# stm32f407z.net
KiCad netlist of a schematic drawn in Altium Designer
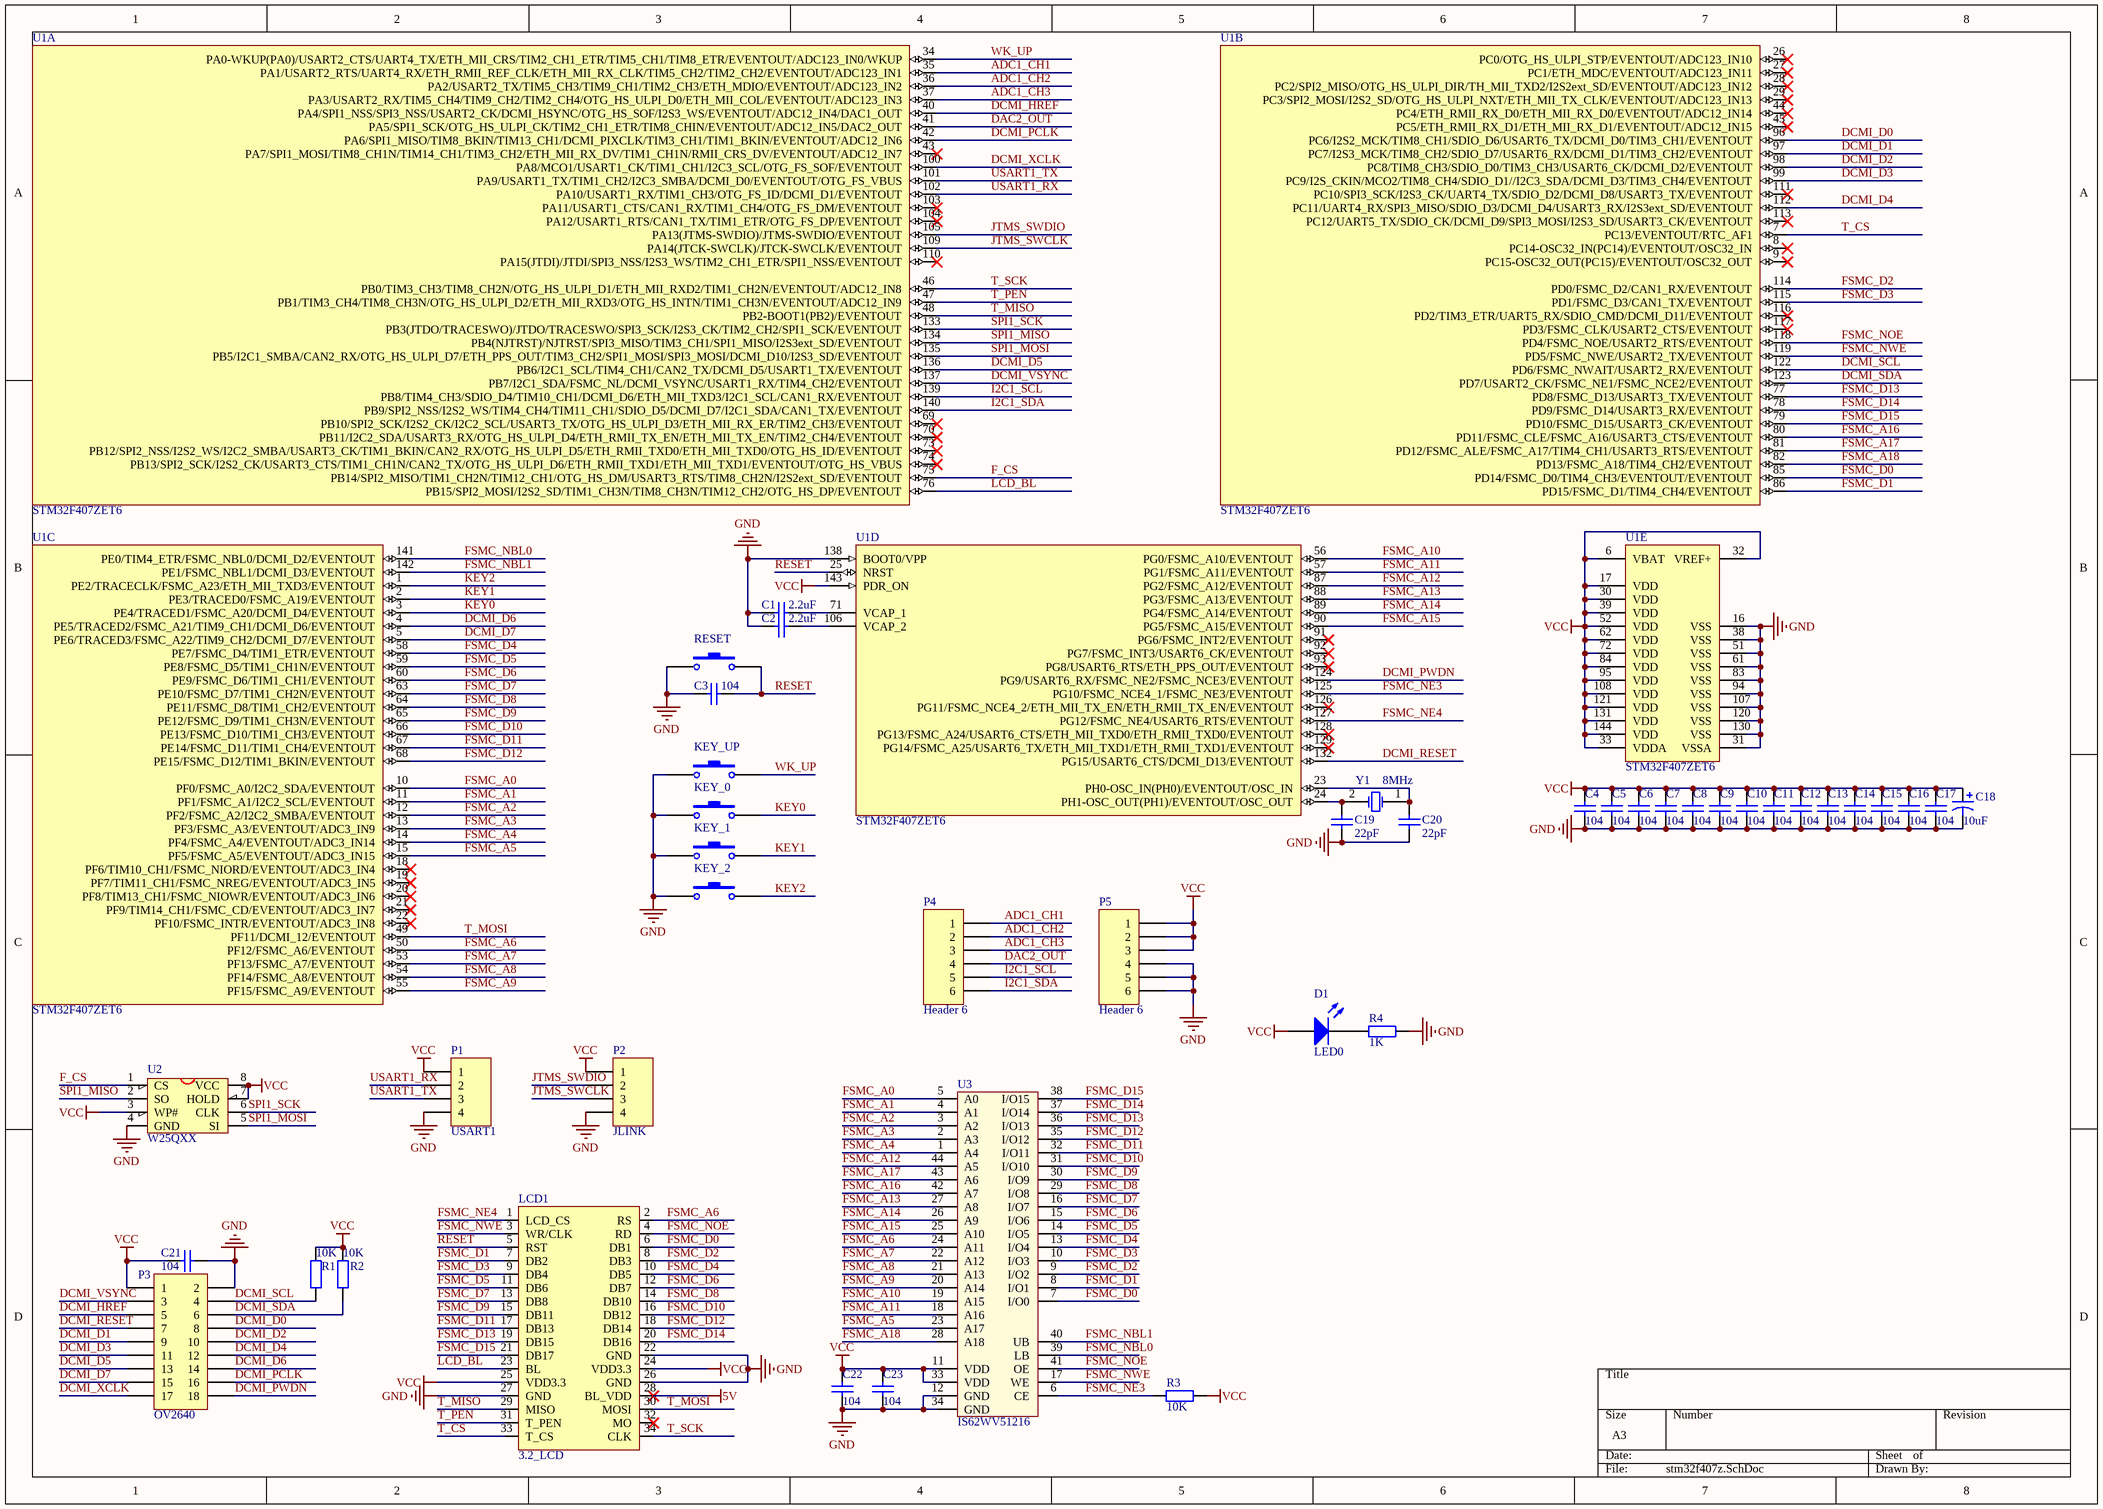
[diagram p0: stm32f407z.SchDoc]

(export (version "E")
  (design (tool "Eeschema 10.0.6"))
  (components
    (comp (ref "C1")
      (value "2.2uF")
      (footprint "C0603")
      (description "Capacitor")
      (libsource (lib "Miscellaneous Devices") (part "Cap"))
    )
    (comp (ref "C2")
      (value "2.2uF")
      (footprint "C0603")
      (description "Capacitor")
      (libsource (lib "Miscellaneous Devices") (part "Cap"))
    )
    (comp (ref "C3")
      (value "104")
      (footprint "C0603")
      (description "Capacitor")
      (libsource (lib "Miscellaneous Devices") (part "Cap"))
    )
    (comp (ref "C4")
      (value "104")
      (footprint "C0603")
      (description "Capacitor")
      (libsource (lib "Miscellaneous Devices") (part "Cap"))
    )
    (comp (ref "C5")
      (value "104")
      (footprint "C0603")
      (description "Capacitor")
      (libsource (lib "Miscellaneous Devices") (part "Cap"))
    )
    (comp (ref "C6")
      (value "104")
      (footprint "C0603")
      (description "Capacitor")
      (libsource (lib "Miscellaneous Devices") (part "Cap"))
    )
    (comp (ref "C7")
      (value "104")
      (footprint "C0603")
      (description "Capacitor")
      (libsource (lib "Miscellaneous Devices") (part "Cap"))
    )
    (comp (ref "C8")
      (value "104")
      (footprint "C0603")
      (description "Capacitor")
      (libsource (lib "Miscellaneous Devices") (part "Cap"))
    )
    (comp (ref "C9")
      (value "104")
      (footprint "C0603")
      (description "Capacitor")
      (libsource (lib "Miscellaneous Devices") (part "Cap"))
    )
    (comp (ref "C10")
      (value "104")
      (footprint "C0603")
      (description "Capacitor")
      (libsource (lib "Miscellaneous Devices") (part "Cap"))
    )
    (comp (ref "C11")
      (value "104")
      (footprint "C0603")
      (description "Capacitor")
      (libsource (lib "Miscellaneous Devices") (part "Cap"))
    )
    (comp (ref "C12")
      (value "104")
      (footprint "C0603")
      (description "Capacitor")
      (libsource (lib "Miscellaneous Devices") (part "Cap"))
    )
    (comp (ref "C13")
      (value "104")
      (footprint "C0603")
      (description "Capacitor")
      (libsource (lib "Miscellaneous Devices") (part "Cap"))
    )
    (comp (ref "C14")
      (value "104")
      (footprint "C0603")
      (description "Capacitor")
      (libsource (lib "Miscellaneous Devices") (part "Cap"))
    )
    (comp (ref "C15")
      (value "104")
      (footprint "C0603")
      (description "Capacitor")
      (libsource (lib "Miscellaneous Devices") (part "Cap"))
    )
    (comp (ref "C16")
      (value "104")
      (footprint "C0603")
      (description "Capacitor")
      (libsource (lib "Miscellaneous Devices") (part "Cap"))
    )
    (comp (ref "C17")
      (value "104")
      (footprint "C0603")
      (description "Capacitor")
      (libsource (lib "Miscellaneous Devices") (part "Cap"))
    )
    (comp (ref "C18")
      (value "10uF")
      (footprint "LC-CASE-A_3216")
      (description "Polarized Capacitor (Radial)")
      (libsource (lib "Miscellaneous Devices") (part "Cap Pol1"))
    )
    (comp (ref "C19")
      (value "22pF")
      (footprint "C0603")
      (description "Capacitor")
      (libsource (lib "Miscellaneous Devices") (part "Cap"))
    )
    (comp (ref "C20")
      (value "22pF")
      (footprint "C0603")
      (description "Capacitor")
      (libsource (lib "Miscellaneous Devices") (part "Cap"))
    )
    (comp (ref "C21")
      (value "104")
      (footprint "C0603")
      (description "Capacitor")
      (libsource (lib "Miscellaneous Devices") (part "Cap"))
    )
    (comp (ref "C22")
      (value "104")
      (footprint "C0603")
      (description "Capacitor")
      (libsource (lib "Miscellaneous Devices") (part "Cap"))
    )
    (comp (ref "C23")
      (value "104")
      (footprint "C0603")
      (description "Capacitor")
      (libsource (lib "Miscellaneous Devices") (part "Cap"))
    )
    (comp (ref "D1")
      (value "LED0")
      (footprint "LED0603")
      (description "Typical INFRARED GaAs LED")
      (libsource (lib "Miscellaneous Devices") (part "LED0"))
    )
    (comp (ref "KEY_0")
      (value "RESET")
      (footprint "micro button_2_SMD")
      (description "Switch")
      (libsource (lib "Miscellaneous Devices") (part "SW-PB"))
    )
    (comp (ref "KEY_1")
      (value "RESET")
      (footprint "micro button_2_SMD")
      (description "Switch")
      (libsource (lib "Miscellaneous Devices") (part "SW-PB"))
    )
    (comp (ref "KEY_2")
      (value "RESET")
      (footprint "micro button_2_SMD")
      (description "Switch")
      (libsource (lib "Miscellaneous Devices") (part "SW-PB"))
    )
    (comp (ref "KEY_UP")
      (value "RESET")
      (footprint "micro button_2_SMD")
      (description "Switch")
      (libsource (lib "Miscellaneous Devices") (part "SW-PB"))
    )
    (comp (ref "LCD1") (value "3.2_LCD") (footprint "HDR2X17") (libsource (lib "主控板载芯片") (part "3.2_LCD")))
    (comp (ref "P1")
      (value "USART1")
      (footprint "1.25PWT-4P")
      (description "Header, 4-Pin")
      (libsource (lib "Miscellaneous Connectors") (part "Header 4"))
    )
    (comp (ref "P2")
      (value "JLINK")
      (footprint "1.25PWT-4P")
      (description "Header, 4-Pin")
      (libsource (lib "Miscellaneous Connectors") (part "Header 4"))
    )
    (comp (ref "P3")
      (value "OV2640")
      (footprint "HDR2X9")
      (description "Header, 9-Pin, Dual row")
      (libsource (lib "Miscellaneous Connectors") (part "Header 9X2"))
    )
    (comp (ref "P4")
      (value "Header 6")
      (footprint "PIN_6")
      (description "Header, 6-Pin")
      (libsource (lib "Miscellaneous Connectors") (part "Header 6"))
    )
    (comp (ref "P5")
      (value "Header 6")
      (footprint "PIN_6")
      (description "Header, 6-Pin")
      (libsource (lib "Miscellaneous Connectors") (part "Header 6"))
    )
    (comp (ref "R1")
      (value "10K")
      (footprint "R0603")
      (description "Resistor")
      (libsource (lib "Miscellaneous Devices") (part "Res2"))
    )
    (comp (ref "R2")
      (value "10K")
      (footprint "R0603")
      (description "Resistor")
      (libsource (lib "Miscellaneous Devices") (part "Res2"))
    )
    (comp (ref "R3")
      (value "10K")
      (footprint "R0603")
      (description "Resistor")
      (libsource (lib "") (part "Res2_1"))
    )
    (comp (ref "R4")
      (value "1K")
      (footprint "R0603")
      (description "Resistor")
      (libsource (lib "") (part "Res2_1"))
    )
    (comp (ref "RESET")
      (value "RESET")
      (footprint "micro button_2_SMD")
      (description "Switch")
      (libsource (lib "Miscellaneous Devices") (part "SW-PB"))
    )
    (comp (ref "U1")
      (value "STM32F407ZET6")
      (footprint "QFP144-0r5-20X20")
      (libsource (lib "STMicroelectronics STM32 F4") (part "STM32F407ZET6"))
    )
    (comp (ref "U2")
      (value "W25QXX")
      (footprint "SOIC_8")
      (description "W25X16;SST25VF016;MX25L1605")
      (libsource (lib "战舰STM32开发板底板封装库") (part "W25X16"))
    )
    (comp (ref "U3")
      (value "IS62WV51216")
      (footprint "TSOP44-0r8-10")
      (libsource (lib "Explorer STM32F407封装库") (part "IS62WV51216"))
    )
    (comp (ref "Y1")
      (value "8MHz")
      (footprint "Crystal_HC_49USMD")
      (description "Crystal Oscillator")
      (libsource (lib "Miscellaneous Devices") (part "XTAL"))
    )
  )
  (nets
    (net (code "1") (name "/ADC1_CH1") (class "Default")
      (node (ref "P4") (pin "1") (pinfunction "1_1") (pintype "passive"))
      (node (ref "U1") (pin "35") (pinfunction "PA1/USART2_RTS/UART4_RX/ETH_RMII_REF_CLK/ETH_MII_RX_CLK/TIM5_CH2/TIM2_CH2/EVENTOUT/ADC123_IN1_35") (pintype "bidirectional"))
    )
    (net (code "2") (name "/ADC1_CH2") (class "Default")
      (node (ref "P4") (pin "2") (pinfunction "2_2") (pintype "passive"))
      (node (ref "U1") (pin "36") (pinfunction "PA2/USART2_TX/TIM5_CH3/TIM9_CH1/TIM2_CH3/ETH_MDIO/EVENTOUT/ADC123_IN2_36") (pintype "bidirectional"))
    )
    (net (code "3") (name "/ADC1_CH3") (class "Default")
      (node (ref "P4") (pin "3") (pinfunction "3_3") (pintype "passive"))
      (node (ref "U1") (pin "37") (pinfunction "PA3/USART2_RX/TIM5_CH4/TIM9_CH2/TIM2_CH4/OTG_HS_ULPI_D0/ETH_MII_COL/EVENTOUT/ADC123_IN3_37") (pintype "bidirectional"))
    )
    (net (code "4") (name "/DAC2_OUT") (class "Default")
      (node (ref "P4") (pin "4") (pinfunction "4_4") (pintype "passive"))
      (node (ref "U1") (pin "41") (pinfunction "PA5/SPI1_SCK/OTG_HS_ULPI_CK/TIM2_CH1_ETR/TIM8_CHIN/EVENTOUT/ADC12_IN5/DAC2_OUT_41") (pintype "bidirectional"))
    )
    (net (code "5") (name "/DCMI_D0") (class "Default")
      (node (ref "P3") (pin "8") (pinfunction "8_8") (pintype "passive"))
      (node (ref "U1") (pin "96") (pinfunction "PC6/I2S2_MCK/TIM8_CH1/SDIO_D6/USART6_TX/DCMI_D0/TIM3_CH1/EVENTOUT_96") (pintype "bidirectional"))
    )
    (net (code "6") (name "/DCMI_D1") (class "Default")
      (node (ref "P3") (pin "9") (pinfunction "9_9") (pintype "passive"))
      (node (ref "U1") (pin "97") (pinfunction "PC7/I2S3_MCK/TIM8_CH2/SDIO_D7/USART6_RX/DCMI_D1/TIM3_CH2/EVENTOUT_97") (pintype "bidirectional"))
    )
    (net (code "7") (name "/DCMI_D2") (class "Default")
      (node (ref "P3") (pin "10") (pinfunction "10_10") (pintype "passive"))
      (node (ref "U1") (pin "98") (pinfunction "PC8/TIM8_CH3/SDIO_D0/TIM3_CH3/USART6_CK/DCMI_D2/EVENTOUT_98") (pintype "bidirectional"))
    )
    (net (code "8") (name "/DCMI_D3") (class "Default")
      (node (ref "P3") (pin "11") (pinfunction "11_11") (pintype "passive"))
      (node (ref "U1") (pin "99") (pinfunction "PC9/I2S_CKIN/MCO2/TIM8_CH4/SDIO_D1//I2C3_SDA/DCMI_D3/TIM3_CH4/EVENTOUT_99") (pintype "bidirectional"))
    )
    (net (code "9") (name "/DCMI_D4") (class "Default")
      (node (ref "P3") (pin "12") (pinfunction "12_12") (pintype "passive"))
      (node (ref "U1") (pin "112") (pinfunction "PC11/UART4_RX/SPI3_MISO/SDIO_D3/DCMI_D4/USART3_RX/I2S3ext_SD/EVENTOUT_112") (pintype "bidirectional"))
    )
    (net (code "10") (name "/DCMI_D5") (class "Default")
      (node (ref "P3") (pin "13") (pinfunction "13_13") (pintype "passive"))
      (node (ref "U1") (pin "136") (pinfunction "PB6/I2C1_SCL/TIM4_CH1/CAN2_TX/DCMI_D5/USART1_TX/EVENTOUT_136") (pintype "bidirectional"))
    )
    (net (code "11") (name "/DCMI_D6") (class "Default")
      (node (ref "P3") (pin "14") (pinfunction "14_14") (pintype "passive"))
      (node (ref "U1") (pin "4") (pinfunction "PE5/TRACED2/FSMC_A21/TIM9_CH1/DCMI_D6/EVENTOUT_4") (pintype "bidirectional"))
    )
    (net (code "12") (name "/DCMI_D7") (class "Default")
      (node (ref "P3") (pin "15") (pinfunction "15_15") (pintype "passive"))
      (node (ref "U1") (pin "5") (pinfunction "PE6/TRACED3/FSMC_A22/TIM9_CH2/DCMI_D7/EVENTOUT_5") (pintype "bidirectional"))
    )
    (net (code "13") (name "/DCMI_HREF") (class "Default")
      (node (ref "P3") (pin "5") (pinfunction "5_5") (pintype "passive"))
      (node (ref "U1") (pin "40") (pinfunction "PA4/SPI1_NSS/SPI3_NSS/USART2_CK/DCMI_HSYNC/OTG_HS_SOF/I2S3_WS/EVENTOUT/ADC12_IN4/DAC1_OUT_40") (pintype "bidirectional"))
    )
    (net (code "14") (name "/DCMI_PCLK") (class "Default")
      (node (ref "P3") (pin "16") (pinfunction "16_16") (pintype "passive"))
      (node (ref "U1") (pin "42") (pinfunction "PA6/SPI1_MISO/TIM8_BKIN/TIM13_CH1/DCMI_PIXCLK/TIM3_CH1/TIM1_BKIN/EVENTOUT/ADC12_IN6_42") (pintype "bidirectional"))
    )
    (net (code "15") (name "/DCMI_PWDN") (class "Default")
      (node (ref "P3") (pin "18") (pinfunction "18_18") (pintype "passive"))
      (node (ref "U1") (pin "124") (pinfunction "PG9/USART6_RX/FSMC_NE2/FSMC_NCE3/EVENTOUT_124") (pintype "bidirectional"))
    )
    (net (code "16") (name "/DCMI_RESET") (class "Default")
      (node (ref "P3") (pin "7") (pinfunction "7_7") (pintype "passive"))
      (node (ref "U1") (pin "132") (pinfunction "PG15/USART6_CTS/DCMI_D13/EVENTOUT_132") (pintype "bidirectional"))
    )
    (net (code "17") (name "/DCMI_SCL") (class "Default")
      (node (ref "P3") (pin "4") (pinfunction "4_4") (pintype "passive"))
      (node (ref "R1") (pin "1") (pinfunction "1_1") (pintype "passive"))
      (node (ref "U1") (pin "122") (pinfunction "PD6/FSMC_NWAIT/USART2_RX/EVENTOUT_122") (pintype "bidirectional"))
    )
    (net (code "18") (name "/DCMI_SDA") (class "Default")
      (node (ref "P3") (pin "6") (pinfunction "6_6") (pintype "passive"))
      (node (ref "R2") (pin "1") (pinfunction "1_1") (pintype "passive"))
      (node (ref "U1") (pin "123") (pinfunction "PD7/USART2_CK/FSMC_NE1/FSMC_NCE2/EVENTOUT_123") (pintype "bidirectional"))
    )
    (net (code "19") (name "/DCMI_VSYNC") (class "Default")
      (node (ref "P3") (pin "3") (pinfunction "3_3") (pintype "passive"))
      (node (ref "U1") (pin "137") (pinfunction "PB7/I2C1_SDA/FSMC_NL/DCMI_VSYNC/USART1_RX/TIM4_CH2/EVENTOUT_137") (pintype "bidirectional"))
    )
    (net (code "20") (name "/DCMI_XCLK") (class "Default")
      (node (ref "P3") (pin "17") (pinfunction "17_17") (pintype "passive"))
      (node (ref "U1") (pin "100") (pinfunction "PA8/MCO1/USART1_CK/TIM1_CH1/I2C3_SCL/OTG_FS_SOF/EVENTOUT_100") (pintype "bidirectional"))
    )
    (net (code "21") (name "/FSMC_A0") (class "Default")
      (node (ref "U1") (pin "10") (pinfunction "PF0/FSMC_A0/I2C2_SDA/EVENTOUT_10") (pintype "bidirectional"))
      (node (ref "U3") (pin "5") (pinfunction "A0_5") (pintype "passive"))
    )
    (net (code "22") (name "/FSMC_A1") (class "Default")
      (node (ref "U1") (pin "11") (pinfunction "PF1/FSMC_A1/I2C2_SCL/EVENTOUT_11") (pintype "bidirectional"))
      (node (ref "U3") (pin "4") (pinfunction "A1_4") (pintype "passive"))
    )
    (net (code "23") (name "/FSMC_A2") (class "Default")
      (node (ref "U1") (pin "12") (pinfunction "PF2/FSMC_A2/I2C2_SMBA/EVENTOUT_12") (pintype "bidirectional"))
      (node (ref "U3") (pin "3") (pinfunction "A2_3") (pintype "passive"))
    )
    (net (code "24") (name "/FSMC_A3") (class "Default")
      (node (ref "U1") (pin "13") (pinfunction "PF3/FSMC_A3/EVENTOUT/ADC3_IN9_13") (pintype "bidirectional"))
      (node (ref "U3") (pin "2") (pinfunction "A3_2") (pintype "passive"))
    )
    (net (code "25") (name "/FSMC_A4") (class "Default")
      (node (ref "U1") (pin "14") (pinfunction "PF4/FSMC_A4/EVENTOUT/ADC3_IN14_14") (pintype "bidirectional"))
      (node (ref "U3") (pin "1") (pinfunction "A4_1") (pintype "passive"))
    )
    (net (code "26") (name "/FSMC_A5") (class "Default")
      (node (ref "U1") (pin "15") (pinfunction "PF5/FSMC_A5/EVENTOUT/ADC3_IN15_15") (pintype "bidirectional"))
      (node (ref "U3") (pin "23") (pinfunction "A17_23") (pintype "passive"))
    )
    (net (code "27") (name "/FSMC_A6") (class "Default")
      (node (ref "LCD1") (pin "2") (pinfunction "RS_2") (pintype "passive"))
      (node (ref "U1") (pin "50") (pinfunction "PF12/FSMC_A6/EVENTOUT_50") (pintype "bidirectional"))
      (node (ref "U3") (pin "24") (pinfunction "A11_24") (pintype "passive"))
    )
    (net (code "28") (name "/FSMC_A7") (class "Default")
      (node (ref "U1") (pin "53") (pinfunction "PF13/FSMC_A7/EVENTOUT_53") (pintype "bidirectional"))
      (node (ref "U3") (pin "22") (pinfunction "A12_22") (pintype "passive"))
    )
    (net (code "29") (name "/FSMC_A8") (class "Default")
      (node (ref "U1") (pin "54") (pinfunction "PF14/FSMC_A8/EVENTOUT_54") (pintype "bidirectional"))
      (node (ref "U3") (pin "21") (pinfunction "A13_21") (pintype "passive"))
    )
    (net (code "30") (name "/FSMC_A9") (class "Default")
      (node (ref "U1") (pin "55") (pinfunction "PF15/FSMC_A9/EVENTOUT_55") (pintype "bidirectional"))
      (node (ref "U3") (pin "20") (pinfunction "A14_20") (pintype "passive"))
    )
    (net (code "31") (name "/FSMC_A10") (class "Default")
      (node (ref "U1") (pin "56") (pinfunction "PG0/FSMC_A10/EVENTOUT_56") (pintype "bidirectional"))
      (node (ref "U3") (pin "19") (pinfunction "A15_19") (pintype "passive"))
    )
    (net (code "32") (name "/FSMC_A11") (class "Default")
      (node (ref "U1") (pin "57") (pinfunction "PG1/FSMC_A11/EVENTOUT_57") (pintype "bidirectional"))
      (node (ref "U3") (pin "18") (pinfunction "A16_18") (pintype "passive"))
    )
    (net (code "33") (name "/FSMC_A12") (class "Default")
      (node (ref "U1") (pin "87") (pinfunction "PG2/FSMC_A12/EVENTOUT_87") (pintype "bidirectional"))
      (node (ref "U3") (pin "44") (pinfunction "A5_44") (pintype "passive"))
    )
    (net (code "34") (name "/FSMC_A13") (class "Default")
      (node (ref "U1") (pin "88") (pinfunction "PG3/FSMC_A13/EVENTOUT_88") (pintype "bidirectional"))
      (node (ref "U3") (pin "27") (pinfunction "A8_27") (pintype "passive"))
    )
    (net (code "35") (name "/FSMC_A14") (class "Default")
      (node (ref "U1") (pin "89") (pinfunction "PG4/FSMC_A14/EVENTOUT_89") (pintype "bidirectional"))
      (node (ref "U3") (pin "26") (pinfunction "A9_26") (pintype "passive"))
    )
    (net (code "36") (name "/FSMC_A15") (class "Default")
      (node (ref "U1") (pin "90") (pinfunction "PG5/FSMC_A15/EVENTOUT_90") (pintype "bidirectional"))
      (node (ref "U3") (pin "25") (pinfunction "A10_25") (pintype "passive"))
    )
    (net (code "37") (name "/FSMC_A16") (class "Default")
      (node (ref "U1") (pin "80") (pinfunction "PD11/FSMC_CLE/FSMC_A16/USART3_CTS/EVENTOUT_80") (pintype "bidirectional"))
      (node (ref "U3") (pin "42") (pinfunction "A7_42") (pintype "passive"))
    )
    (net (code "38") (name "/FSMC_A17") (class "Default")
      (node (ref "U1") (pin "81") (pinfunction "PD12/FSMC_ALE/FSMC_A17/TIM4_CH1/USART3_RTS/EVENTOUT_81") (pintype "bidirectional"))
      (node (ref "U3") (pin "43") (pinfunction "A6_43") (pintype "passive"))
    )
    (net (code "39") (name "/FSMC_A18") (class "Default")
      (node (ref "U1") (pin "82") (pinfunction "PD13/FSMC_A18/TIM4_CH2/EVENTOUT_82") (pintype "bidirectional"))
      (node (ref "U3") (pin "28") (pinfunction "A18_28") (pintype "passive"))
    )
    (net (code "40") (name "/FSMC_D0") (class "Default")
      (node (ref "LCD1") (pin "6") (pinfunction "DB1_6") (pintype "passive"))
      (node (ref "U1") (pin "85") (pinfunction "PD14/FSMC_D0/TIM4_CH3/EVENTOUT/EVENTOUT_85") (pintype "bidirectional"))
      (node (ref "U3") (pin "7") (pinfunction "I/O0_7") (pintype "passive"))
    )
    (net (code "41") (name "/FSMC_D1") (class "Default")
      (node (ref "LCD1") (pin "7") (pinfunction "DB2_7") (pintype "passive"))
      (node (ref "U1") (pin "86") (pinfunction "PD15/FSMC_D1/TIM4_CH4/EVENTOUT_86") (pintype "bidirectional"))
      (node (ref "U3") (pin "8") (pinfunction "I/O1_8") (pintype "passive"))
    )
    (net (code "42") (name "/FSMC_D2") (class "Default")
      (node (ref "LCD1") (pin "8") (pinfunction "DB3_8") (pintype "passive"))
      (node (ref "U1") (pin "114") (pinfunction "PD0/FSMC_D2/CAN1_RX/EVENTOUT_114") (pintype "bidirectional"))
      (node (ref "U3") (pin "9") (pinfunction "I/O2_9") (pintype "passive"))
    )
    (net (code "43") (name "/FSMC_D3") (class "Default")
      (node (ref "LCD1") (pin "9") (pinfunction "DB4_9") (pintype "passive"))
      (node (ref "U1") (pin "115") (pinfunction "PD1/FSMC_D3/CAN1_TX/EVENTOUT_115") (pintype "bidirectional"))
      (node (ref "U3") (pin "10") (pinfunction "I/O3_10") (pintype "passive"))
    )
    (net (code "44") (name "/FSMC_D4") (class "Default")
      (node (ref "LCD1") (pin "10") (pinfunction "DB5_10") (pintype "passive"))
      (node (ref "U1") (pin "58") (pinfunction "PE7/FSMC_D4/TIM1_ETR/EVENTOUT_58") (pintype "bidirectional"))
      (node (ref "U3") (pin "13") (pinfunction "I/O4_13") (pintype "passive"))
    )
    (net (code "45") (name "/FSMC_D5") (class "Default")
      (node (ref "LCD1") (pin "11") (pinfunction "DB6_11") (pintype "passive"))
      (node (ref "U1") (pin "59") (pinfunction "PE8/FSMC_D5/TIM1_CH1N/EVENTOUT_59") (pintype "bidirectional"))
      (node (ref "U3") (pin "14") (pinfunction "I/O5_14") (pintype "passive"))
    )
    (net (code "46") (name "/FSMC_D6") (class "Default")
      (node (ref "LCD1") (pin "12") (pinfunction "DB7_12") (pintype "passive"))
      (node (ref "U1") (pin "60") (pinfunction "PE9/FSMC_D6/TIM1_CH1/EVENTOUT_60") (pintype "bidirectional"))
      (node (ref "U3") (pin "15") (pinfunction "I/O6_15") (pintype "passive"))
    )
    (net (code "47") (name "/FSMC_D7") (class "Default")
      (node (ref "LCD1") (pin "13") (pinfunction "DB8_13") (pintype "passive"))
      (node (ref "U1") (pin "63") (pinfunction "PE10/FSMC_D7/TIM1_CH2N/EVENTOUT_63") (pintype "bidirectional"))
      (node (ref "U3") (pin "16") (pinfunction "I/O7_16") (pintype "passive"))
    )
    (net (code "48") (name "/FSMC_D8") (class "Default")
      (node (ref "LCD1") (pin "14") (pinfunction "DB10_14") (pintype "passive"))
      (node (ref "U1") (pin "64") (pinfunction "PE11/FSMC_D8/TIM1_CH2/EVENTOUT_64") (pintype "bidirectional"))
      (node (ref "U3") (pin "29") (pinfunction "I/O8_29") (pintype "passive"))
    )
    (net (code "49") (name "/FSMC_D9") (class "Default")
      (node (ref "LCD1") (pin "15") (pinfunction "DB11_15") (pintype "passive"))
      (node (ref "U1") (pin "65") (pinfunction "PE12/FSMC_D9/TIM1_CH3N/EVENTOUT_65") (pintype "bidirectional"))
      (node (ref "U3") (pin "30") (pinfunction "I/O9_30") (pintype "passive"))
    )
    (net (code "50") (name "/FSMC_D10") (class "Default")
      (node (ref "LCD1") (pin "16") (pinfunction "DB12_16") (pintype "passive"))
      (node (ref "U1") (pin "66") (pinfunction "PE13/FSMC_D10/TIM1_CH3/EVENTOUT_66") (pintype "bidirectional"))
      (node (ref "U3") (pin "31") (pinfunction "I/O10_31") (pintype "passive"))
    )
    (net (code "51") (name "/FSMC_D11") (class "Default")
      (node (ref "LCD1") (pin "17") (pinfunction "DB13_17") (pintype "passive"))
      (node (ref "U1") (pin "67") (pinfunction "PE14/FSMC_D11/TIM1_CH4/EVENTOUT_67") (pintype "bidirectional"))
      (node (ref "U3") (pin "32") (pinfunction "I/O11_32") (pintype "passive"))
    )
    (net (code "52") (name "/FSMC_D12") (class "Default")
      (node (ref "LCD1") (pin "18") (pinfunction "DB14_18") (pintype "passive"))
      (node (ref "U1") (pin "68") (pinfunction "PE15/FSMC_D12/TIM1_BKIN/EVENTOUT_68") (pintype "bidirectional"))
      (node (ref "U3") (pin "35") (pinfunction "I/O12_35") (pintype "passive"))
    )
    (net (code "53") (name "/FSMC_D13") (class "Default")
      (node (ref "LCD1") (pin "19") (pinfunction "DB15_19") (pintype "passive"))
      (node (ref "U1") (pin "77") (pinfunction "PD8/FSMC_D13/USART3_TX/EVENTOUT_77") (pintype "bidirectional"))
      (node (ref "U3") (pin "36") (pinfunction "I/O13_36") (pintype "passive"))
    )
    (net (code "54") (name "/FSMC_D14") (class "Default")
      (node (ref "LCD1") (pin "20") (pinfunction "DB16_20") (pintype "passive"))
      (node (ref "U1") (pin "78") (pinfunction "PD9/FSMC_D14/USART3_RX/EVENTOUT_78") (pintype "bidirectional"))
      (node (ref "U3") (pin "37") (pinfunction "I/O14_37") (pintype "passive"))
    )
    (net (code "55") (name "/FSMC_D15") (class "Default")
      (node (ref "LCD1") (pin "21") (pinfunction "DB17_21") (pintype "passive"))
      (node (ref "U1") (pin "79") (pinfunction "PD10/FSMC_D15/USART3_CK/EVENTOUT_79") (pintype "bidirectional"))
      (node (ref "U3") (pin "38") (pinfunction "I/O15_38") (pintype "passive"))
    )
    (net (code "56") (name "/FSMC_NBL0") (class "Default")
      (node (ref "U1") (pin "141") (pinfunction "PE0/TIM4_ETR/FSMC_NBL0/DCMI_D2/EVENTOUT_141") (pintype "bidirectional"))
      (node (ref "U3") (pin "39") (pinfunction "LB_39") (pintype "passive"))
    )
    (net (code "57") (name "/FSMC_NBL1") (class "Default")
      (node (ref "U1") (pin "142") (pinfunction "PE1/FSMC_NBL1/DCMI_D3/EVENTOUT_142") (pintype "bidirectional"))
      (node (ref "U3") (pin "40") (pinfunction "UB_40") (pintype "passive"))
    )
    (net (code "58") (name "/FSMC_NE3") (class "Default")
      (node (ref "R3") (pin "2") (pinfunction "2_2") (pintype "passive"))
      (node (ref "U1") (pin "125") (pinfunction "PG10/FSMC_NCE4_1/FSMC_NE3/EVENTOUT_125") (pintype "bidirectional"))
      (node (ref "U3") (pin "6") (pinfunction "CE_6") (pintype "passive"))
    )
    (net (code "59") (name "/FSMC_NE4") (class "Default")
      (node (ref "LCD1") (pin "1") (pinfunction "LCD_CS_1") (pintype "passive"))
      (node (ref "U1") (pin "127") (pinfunction "PG12/FSMC_NE4/USART6_RTS/EVENTOUT_127") (pintype "bidirectional"))
    )
    (net (code "60") (name "/FSMC_NOE") (class "Default")
      (node (ref "LCD1") (pin "4") (pinfunction "RD_4") (pintype "passive"))
      (node (ref "U1") (pin "118") (pinfunction "PD4/FSMC_NOE/USART2_RTS/EVENTOUT_118") (pintype "bidirectional"))
      (node (ref "U3") (pin "41") (pinfunction "OE_41") (pintype "passive"))
    )
    (net (code "61") (name "/FSMC_NWE") (class "Default")
      (node (ref "LCD1") (pin "3") (pinfunction "WR/CLK_3") (pintype "passive"))
      (node (ref "U1") (pin "119") (pinfunction "PD5/FSMC_NWE/USART2_TX/EVENTOUT_119") (pintype "bidirectional"))
      (node (ref "U3") (pin "17") (pinfunction "WE_17") (pintype "passive"))
    )
    (net (code "62") (name "/F_CS") (class "Default")
      (node (ref "U1") (pin "75") (pinfunction "PB14/SPI2_MISO/TIM1_CH2N/TIM12_CH1/OTG_HS_DM/USART3_RTS/TIM8_CH2N/I2S2ext_SD/EVENTOUT_75") (pintype "bidirectional"))
      (node (ref "U2") (pin "1") (pinfunction "CS_1") (pintype "passive"))
    )
    (net (code "63") (name "/I2C1_SCL") (class "Default")
      (node (ref "P4") (pin "5") (pinfunction "5_5") (pintype "passive"))
      (node (ref "U1") (pin "139") (pinfunction "PB8/TIM4_CH3/SDIO_D4/TIM10_CH1/DCMI_D6/ETH_MII_TXD3/I2C1_SCL/CAN1_RX/EVENTOUT_139") (pintype "bidirectional"))
    )
    (net (code "64") (name "/I2C1_SDA") (class "Default")
      (node (ref "P4") (pin "6") (pinfunction "6_6") (pintype "passive"))
      (node (ref "U1") (pin "140") (pinfunction "PB9/SPI2_NSS/I2S2_WS/TIM4_CH4/TIM11_CH1/SDIO_D5/DCMI_D7/I2C1_SDA/CAN1_TX/EVENTOUT_140") (pintype "bidirectional"))
    )
    (net (code "65") (name "/JTMS_SWCLK") (class "Default")
      (node (ref "P2") (pin "3") (pinfunction "3_3") (pintype "passive"))
      (node (ref "U1") (pin "109") (pinfunction "PA14(JTCK-SWCLK)/JTCK-SWCLK/EVENTOUT_109") (pintype "bidirectional"))
    )
    (net (code "66") (name "/JTMS_SWDIO") (class "Default")
      (node (ref "P2") (pin "2") (pinfunction "2_2") (pintype "passive"))
      (node (ref "U1") (pin "105") (pinfunction "PA13(JTMS-SWDIO)/JTMS-SWDIO/EVENTOUT_105") (pintype "bidirectional"))
    )
    (net (code "67") (name "/KEY0") (class "Default")
      (node (ref "KEY_0") (pin "2") (pinfunction "2_2") (pintype "passive"))
      (node (ref "U1") (pin "3") (pinfunction "PE4/TRACED1/FSMC_A20/DCMI_D4/EVENTOUT_3") (pintype "bidirectional"))
    )
    (net (code "68") (name "/KEY1") (class "Default")
      (node (ref "KEY_1") (pin "2") (pinfunction "2_2") (pintype "passive"))
      (node (ref "U1") (pin "2") (pinfunction "PE3/TRACED0/FSMC_A19/EVENTOUT_2") (pintype "bidirectional"))
    )
    (net (code "69") (name "/KEY2") (class "Default")
      (node (ref "KEY_2") (pin "2") (pinfunction "2_2") (pintype "passive"))
      (node (ref "U1") (pin "1") (pinfunction "PE2/TRACECLK/FSMC_A23/ETH_MII_TXD3/EVENTOUT_1") (pintype "bidirectional"))
    )
    (net (code "70") (name "/LCD_BL") (class "Default")
      (node (ref "LCD1") (pin "23") (pinfunction "BL_23") (pintype "passive"))
      (node (ref "U1") (pin "76") (pinfunction "PB15/SPI2_MOSI/I2S2_SD/TIM1_CH3N/TIM8_CH3N/TIM12_CH2/OTG_HS_DP/EVENTOUT_76") (pintype "bidirectional"))
    )
    (net (code "71") (name "/RESET") (class "Default")
      (node (ref "C3") (pin "2") (pinfunction "2_2") (pintype "passive"))
      (node (ref "LCD1") (pin "5") (pinfunction "RST_5") (pintype "passive"))
      (node (ref "RESET") (pin "2") (pinfunction "2_2") (pintype "passive"))
      (node (ref "U1") (pin "25") (pinfunction "NRST_25") (pintype "bidirectional"))
    )
    (net (code "72") (name "/SPI1_MISO") (class "Default")
      (node (ref "U1") (pin "134") (pinfunction "PB4(NJTRST)/NJTRST/SPI3_MISO/TIM3_CH1/SPI1_MISO/I2S3ext_SD/EVENTOUT_134") (pintype "bidirectional"))
      (node (ref "U2") (pin "2") (pinfunction "SO_2") (pintype "passive"))
    )
    (net (code "73") (name "/SPI1_MOSI") (class "Default")
      (node (ref "U1") (pin "135") (pinfunction "PB5/I2C1_SMBA/CAN2_RX/OTG_HS_ULPI_D7/ETH_PPS_OUT/TIM3_CH2/SPI1_MOSI/SPI3_MOSI/DCMI_D10/I2S3_SD/EVENTOUT_135") (pintype "bidirectional"))
      (node (ref "U2") (pin "5") (pinfunction "SI_5") (pintype "passive"))
    )
    (net (code "74") (name "/SPI1_SCK") (class "Default")
      (node (ref "U1") (pin "133") (pinfunction "PB3(JTDO/TRACESWO)/JTDO/TRACESWO/SPI3_SCK/I2S3_CK/TIM2_CH2/SPI1_SCK/EVENTOUT_133") (pintype "bidirectional"))
      (node (ref "U2") (pin "6") (pinfunction "CLK_6") (pintype "passive"))
    )
    (net (code "75") (name "/T_CS") (class "Default")
      (node (ref "LCD1") (pin "33") (pinfunction "T_CS_33") (pintype "passive"))
      (node (ref "U1") (pin "7") (pinfunction "PC13/EVENTOUT/RTC_AF1_7") (pintype "bidirectional"))
    )
    (net (code "76") (name "/T_MISO") (class "Default")
      (node (ref "LCD1") (pin "29") (pinfunction "MISO_29") (pintype "passive"))
      (node (ref "U1") (pin "48") (pinfunction "PB2-BOOT1(PB2)/EVENTOUT_48") (pintype "bidirectional"))
    )
    (net (code "77") (name "/T_MOSI") (class "Default")
      (node (ref "LCD1") (pin "30") (pinfunction "MOSI_30") (pintype "passive"))
      (node (ref "U1") (pin "49") (pinfunction "PF11/DCMI_12/EVENTOUT_49") (pintype "bidirectional"))
    )
    (net (code "78") (name "/T_PEN") (class "Default")
      (node (ref "LCD1") (pin "31") (pinfunction "T_PEN_31") (pintype "passive"))
      (node (ref "U1") (pin "47") (pinfunction "PB1/TIM3_CH4/TIM8_CH3N/OTG_HS_ULPI_D2/ETH_MII_RXD3/OTG_HS_INTN/TIM1_CH3N/EVENTOUT/ADC12_IN9_47") (pintype "bidirectional"))
    )
    (net (code "79") (name "/T_SCK") (class "Default")
      (node (ref "LCD1") (pin "34") (pinfunction "CLK_34") (pintype "passive"))
      (node (ref "U1") (pin "46") (pinfunction "PB0/TIM3_CH3/TIM8_CH2N/OTG_HS_ULPI_D1/ETH_MII_RXD2/TIM1_CH2N/EVENTOUT/ADC12_IN8_46") (pintype "bidirectional"))
    )
    (net (code "80") (name "/USART1_RX") (class "Default")
      (node (ref "P1") (pin "2") (pinfunction "2_2") (pintype "passive"))
      (node (ref "U1") (pin "102") (pinfunction "PA10/USART1_RX/TIM1_CH3/OTG_FS_ID/DCMI_D1/EVENTOUT_102") (pintype "bidirectional"))
    )
    (net (code "81") (name "/USART1_TX") (class "Default")
      (node (ref "P1") (pin "3") (pinfunction "3_3") (pintype "passive"))
      (node (ref "U1") (pin "101") (pinfunction "PA9/USART1_TX/TIM1_CH2/I2C3_SMBA/DCMI_D0/EVENTOUT/OTG_FS_VBUS_101") (pintype "bidirectional"))
    )
    (net (code "82") (name "/WK_UP") (class "Default")
      (node (ref "KEY_UP") (pin "2") (pinfunction "2_2") (pintype "passive"))
      (node (ref "U1") (pin "34") (pinfunction "PA0-WKUP(PA0)/USART2_CTS/UART4_TX/ETH_MII_CRS/TIM2_CH1_ETR/TIM5_CH1/TIM8_ETR/EVENTOUT/ADC123_IN0/WKUP_34") (pintype "bidirectional"))
    )
    (net (code "83") (name "5V") (class "Default")
      (node (ref "LCD1") (pin "28") (pinfunction "BL_VDD_28") (pintype "passive"))
    )
    (net (code "84") (name "GND") (class "Default")
      (node (ref "C1") (pin "1") (pinfunction "1_1") (pintype "passive"))
      (node (ref "C10") (pin "1") (pinfunction "1_1") (pintype "passive"))
      (node (ref "C11") (pin "1") (pinfunction "1_1") (pintype "passive"))
      (node (ref "C12") (pin "1") (pinfunction "1_1") (pintype "passive"))
      (node (ref "C13") (pin "1") (pinfunction "1_1") (pintype "passive"))
      (node (ref "C14") (pin "1") (pinfunction "1_1") (pintype "passive"))
      (node (ref "C15") (pin "1") (pinfunction "1_1") (pintype "passive"))
      (node (ref "C16") (pin "1") (pinfunction "1_1") (pintype "passive"))
      (node (ref "C17") (pin "1") (pinfunction "1_1") (pintype "passive"))
      (node (ref "C18") (pin "2") (pinfunction "2_2") (pintype "passive"))
      (node (ref "C19") (pin "1") (pinfunction "1_1") (pintype "passive"))
      (node (ref "C2") (pin "1") (pinfunction "1_1") (pintype "passive"))
      (node (ref "C20") (pin "1") (pinfunction "1_1") (pintype "passive"))
      (node (ref "C21") (pin "1") (pinfunction "1_1") (pintype "passive"))
      (node (ref "C22") (pin "1") (pinfunction "1_1") (pintype "passive"))
      (node (ref "C23") (pin "1") (pinfunction "1_1") (pintype "passive"))
      (node (ref "C3") (pin "1") (pinfunction "1_1") (pintype "passive"))
      (node (ref "C4") (pin "1") (pinfunction "1_1") (pintype "passive"))
      (node (ref "C5") (pin "1") (pinfunction "1_1") (pintype "passive"))
      (node (ref "C6") (pin "1") (pinfunction "1_1") (pintype "passive"))
      (node (ref "C7") (pin "1") (pinfunction "1_1") (pintype "passive"))
      (node (ref "C8") (pin "1") (pinfunction "1_1") (pintype "passive"))
      (node (ref "C9") (pin "1") (pinfunction "1_1") (pintype "passive"))
      (node (ref "KEY_0") (pin "1") (pinfunction "1_1") (pintype "passive"))
      (node (ref "KEY_1") (pin "1") (pinfunction "1_1") (pintype "passive"))
      (node (ref "KEY_2") (pin "1") (pinfunction "1_1") (pintype "passive"))
      (node (ref "KEY_UP") (pin "1") (pinfunction "1_1") (pintype "passive"))
      (node (ref "LCD1") (pin "22") (pinfunction "GND_22") (pintype "passive"))
      (node (ref "LCD1") (pin "26") (pinfunction "GND_26") (pintype "passive"))
      (node (ref "LCD1") (pin "27") (pinfunction "GND_27") (pintype "passive"))
      (node (ref "P1") (pin "4") (pinfunction "4_4") (pintype "passive"))
      (node (ref "P2") (pin "4") (pinfunction "4_4") (pintype "passive"))
      (node (ref "P3") (pin "2") (pinfunction "2_2") (pintype "passive"))
      (node (ref "P5") (pin "4") (pinfunction "4_4") (pintype "passive"))
      (node (ref "P5") (pin "5") (pinfunction "5_5") (pintype "passive"))
      (node (ref "P5") (pin "6") (pinfunction "6_6") (pintype "passive"))
      (node (ref "R4") (pin "1") (pinfunction "1_1") (pintype "passive"))
      (node (ref "RESET") (pin "1") (pinfunction "1_1") (pintype "passive"))
      (node (ref "U1") (pin "107") (pinfunction "VSS_107") (pintype "power_in"))
      (node (ref "U1") (pin "120") (pinfunction "VSS_120") (pintype "power_in"))
      (node (ref "U1") (pin "130") (pinfunction "VSS_130") (pintype "power_in"))
      (node (ref "U1") (pin "138") (pinfunction "BOOT0/VPP_138") (pintype "input"))
      (node (ref "U1") (pin "16") (pinfunction "VSS_16") (pintype "power_in"))
      (node (ref "U1") (pin "31") (pinfunction "VSSA_31") (pintype "power_in"))
      (node (ref "U1") (pin "38") (pinfunction "VSS_38") (pintype "power_in"))
      (node (ref "U1") (pin "51") (pinfunction "VSS_51") (pintype "power_in"))
      (node (ref "U1") (pin "61") (pinfunction "VSS_61") (pintype "power_in"))
      (node (ref "U1") (pin "83") (pinfunction "VSS_83") (pintype "power_in"))
      (node (ref "U1") (pin "94") (pinfunction "VSS_94") (pintype "power_in"))
      (node (ref "U2") (pin "4") (pinfunction "GND_4") (pintype "passive"))
      (node (ref "U3") (pin "12") (pinfunction "GND_12") (pintype "passive"))
      (node (ref "U3") (pin "34") (pinfunction "GND_34") (pintype "passive"))
    )
    (net (code "85") (name "Net-(D1-K)") (class "Default")
      (node (ref "D1") (pin "2") (pinfunction "K_2") (pintype "passive"))
      (node (ref "R4") (pin "2") (pinfunction "2_2") (pintype "passive"))
    )
    (net (code "86") (name "Net-(U1D-PH0-OSC_IN(PH0){slash}EVENTOUT{slash}OSC_IN)") (class "Default")
      (node (ref "C20") (pin "2") (pinfunction "2_2") (pintype "passive"))
      (node (ref "U1") (pin "23") (pinfunction "PH0-OSC_IN(PH0)/EVENTOUT/OSC_IN_23") (pintype "bidirectional"))
      (node (ref "Y1") (pin "1") (pinfunction "OSC1_1") (pintype "passive"))
    )
    (net (code "87") (name "Net-(U1D-PH1-OSC_OUT(PH1){slash}EVENTOUT{slash}OSC_OUT)") (class "Default")
      (node (ref "C19") (pin "2") (pinfunction "2_2") (pintype "passive"))
      (node (ref "U1") (pin "24") (pinfunction "PH1-OSC_OUT(PH1)/EVENTOUT/OSC_OUT_24") (pintype "bidirectional"))
      (node (ref "Y1") (pin "2") (pinfunction "OSC2_2") (pintype "passive"))
    )
    (net (code "88") (name "Net-(U1D-VCAP_1)") (class "Default")
      (node (ref "C1") (pin "2") (pinfunction "2_2") (pintype "passive"))
      (node (ref "U1") (pin "71") (pinfunction "VCAP_1_71") (pintype "power_in"))
    )
    (net (code "89") (name "Net-(U1D-VCAP_2)") (class "Default")
      (node (ref "C2") (pin "2") (pinfunction "2_2") (pintype "passive"))
      (node (ref "U1") (pin "106") (pinfunction "VCAP_2_106") (pintype "power_in"))
    )
    (net (code "90") (name "VCC") (class "Default")
      (node (ref "C10") (pin "2") (pinfunction "2_2") (pintype "passive"))
      (node (ref "C11") (pin "2") (pinfunction "2_2") (pintype "passive"))
      (node (ref "C12") (pin "2") (pinfunction "2_2") (pintype "passive"))
      (node (ref "C13") (pin "2") (pinfunction "2_2") (pintype "passive"))
      (node (ref "C14") (pin "2") (pinfunction "2_2") (pintype "passive"))
      (node (ref "C15") (pin "2") (pinfunction "2_2") (pintype "passive"))
      (node (ref "C16") (pin "2") (pinfunction "2_2") (pintype "passive"))
      (node (ref "C17") (pin "2") (pinfunction "2_2") (pintype "passive"))
      (node (ref "C18") (pin "1") (pinfunction "1_1") (pintype "passive"))
      (node (ref "C21") (pin "2") (pinfunction "2_2") (pintype "passive"))
      (node (ref "C22") (pin "2") (pinfunction "2_2") (pintype "passive"))
      (node (ref "C23") (pin "2") (pinfunction "2_2") (pintype "passive"))
      (node (ref "C4") (pin "2") (pinfunction "2_2") (pintype "passive"))
      (node (ref "C5") (pin "2") (pinfunction "2_2") (pintype "passive"))
      (node (ref "C6") (pin "2") (pinfunction "2_2") (pintype "passive"))
      (node (ref "C7") (pin "2") (pinfunction "2_2") (pintype "passive"))
      (node (ref "C8") (pin "2") (pinfunction "2_2") (pintype "passive"))
      (node (ref "C9") (pin "2") (pinfunction "2_2") (pintype "passive"))
      (node (ref "D1") (pin "1") (pinfunction "A_1") (pintype "passive"))
      (node (ref "LCD1") (pin "24") (pinfunction "VDD3.3_24") (pintype "passive"))
      (node (ref "LCD1") (pin "25") (pinfunction "VDD3.3_25") (pintype "passive"))
      (node (ref "P1") (pin "1") (pinfunction "1_1") (pintype "passive"))
      (node (ref "P2") (pin "1") (pinfunction "1_1") (pintype "passive"))
      (node (ref "P3") (pin "1") (pinfunction "1_1") (pintype "passive"))
      (node (ref "P5") (pin "1") (pinfunction "1_1") (pintype "passive"))
      (node (ref "P5") (pin "2") (pinfunction "2_2") (pintype "passive"))
      (node (ref "P5") (pin "3") (pinfunction "3_3") (pintype "passive"))
      (node (ref "R1") (pin "2") (pinfunction "2_2") (pintype "passive"))
      (node (ref "R2") (pin "2") (pinfunction "2_2") (pintype "passive"))
      (node (ref "R3") (pin "1") (pinfunction "1_1") (pintype "passive"))
      (node (ref "U1") (pin "108") (pinfunction "VDD_108") (pintype "power_in"))
      (node (ref "U1") (pin "121") (pinfunction "VDD_121") (pintype "power_in"))
      (node (ref "U1") (pin "131") (pinfunction "VDD_131") (pintype "power_in"))
      (node (ref "U1") (pin "143") (pinfunction "PDR_ON_143") (pintype "input"))
      (node (ref "U1") (pin "144") (pinfunction "VDD_144") (pintype "power_in"))
      (node (ref "U1") (pin "17") (pinfunction "VDD_17") (pintype "power_in"))
      (node (ref "U1") (pin "30") (pinfunction "VDD_30") (pintype "power_in"))
      (node (ref "U1") (pin "32") (pinfunction "VREF+_32") (pintype "power_in"))
      (node (ref "U1") (pin "33") (pinfunction "VDDA_33") (pintype "power_in"))
      (node (ref "U1") (pin "39") (pinfunction "VDD_39") (pintype "power_in"))
      (node (ref "U1") (pin "52") (pinfunction "VDD_52") (pintype "power_in"))
      (node (ref "U1") (pin "6") (pinfunction "VBAT_6") (pintype "power_in"))
      (node (ref "U1") (pin "62") (pinfunction "VDD_62") (pintype "power_in"))
      (node (ref "U1") (pin "72") (pinfunction "VDD_72") (pintype "power_in"))
      (node (ref "U1") (pin "84") (pinfunction "VDD_84") (pintype "power_in"))
      (node (ref "U1") (pin "95") (pinfunction "VDD_95") (pintype "power_in"))
      (node (ref "U2") (pin "3") (pinfunction "WP#_3") (pintype "passive"))
      (node (ref "U2") (pin "7") (pinfunction "HOLD_7") (pintype "passive"))
      (node (ref "U2") (pin "8") (pinfunction "VCC_8") (pintype "passive"))
      (node (ref "U3") (pin "11") (pinfunction "VDD_11") (pintype "passive"))
      (node (ref "U3") (pin "33") (pinfunction "VDD_33") (pintype "passive"))
    )
    (net (code "91") (name "unconnected-(LCD1-MO-Pad32)") (class "Default")
      (node (ref "LCD1") (pin "32") (pinfunction "MO_32") (pintype "passive+no_connect"))
    )
    (net (code "92") (name "unconnected-(U1A-PA7{slash}SPI1_MOSI{slash}TIM8_CH1N{slash}TIM14_CH1{slash}TIM3_CH2{slash}ETH_MII_RX_DV{slash}TIM1_CH1N{slash}RMII_CRS_DV{slash}EVENTOUT{slash}ADC12_IN7-Pad43)") (class "Default")
      (node (ref "U1") (pin "43") (pinfunction "PA7/SPI1_MOSI/TIM8_CH1N/TIM14_CH1/TIM3_CH2/ETH_MII_RX_DV/TIM1_CH1N/RMII_CRS_DV/EVENTOUT/ADC12_IN7_43") (pintype "bidirectional+no_connect"))
    )
    (net (code "93") (name "unconnected-(U1A-PA11{slash}USART1_CTS{slash}CAN1_RX{slash}TIM1_CH4{slash}OTG_FS_DM{slash}EVENTOUT-Pad103)") (class "Default")
      (node (ref "U1") (pin "103") (pinfunction "PA11/USART1_CTS/CAN1_RX/TIM1_CH4/OTG_FS_DM/EVENTOUT_103") (pintype "bidirectional+no_connect"))
    )
    (net (code "94") (name "unconnected-(U1A-PA12{slash}USART1_RTS{slash}CAN1_TX{slash}TIM1_ETR{slash}OTG_FS_DP{slash}EVENTOUT-Pad104)") (class "Default")
      (node (ref "U1") (pin "104") (pinfunction "PA12/USART1_RTS/CAN1_TX/TIM1_ETR/OTG_FS_DP/EVENTOUT_104") (pintype "bidirectional+no_connect"))
    )
    (net (code "95") (name "unconnected-(U1A-PA15(JTDI){slash}JTDI{slash}SPI3_NSS{slash}I2S3_WS{slash}TIM2_CH1_ETR{slash}SPI1_NSS{slash}EVENTOUT-Pad110)") (class "Default")
      (node (ref "U1") (pin "110") (pinfunction "PA15(JTDI)/JTDI/SPI3_NSS/I2S3_WS/TIM2_CH1_ETR/SPI1_NSS/EVENTOUT_110") (pintype "bidirectional+no_connect"))
    )
    (net (code "96") (name "unconnected-(U1A-PB10{slash}SPI2_SCK{slash}I2S2_CK{slash}I2C2_SCL{slash}USART3_TX{slash}OTG_HS_ULPI_D3{slash}ETH_MII_RX_ER{slash}TIM2_CH3{slash}EVENTOUT-Pad69)") (class "Default")
      (node (ref "U1") (pin "69") (pinfunction "PB10/SPI2_SCK/I2S2_CK/I2C2_SCL/USART3_TX/OTG_HS_ULPI_D3/ETH_MII_RX_ER/TIM2_CH3/EVENTOUT_69") (pintype "bidirectional+no_connect"))
    )
    (net (code "97") (name "unconnected-(U1A-PB11{slash}I2C2_SDA{slash}USART3_RX{slash}OTG_HS_ULPI_D4{slash}ETH_RMII_TX_EN{slash}ETH_MII_TX_EN{slash}TIM2_CH4{slash}EVENTOUT-Pad70)") (class "Default")
      (node (ref "U1") (pin "70") (pinfunction "PB11/I2C2_SDA/USART3_RX/OTG_HS_ULPI_D4/ETH_RMII_TX_EN/ETH_MII_TX_EN/TIM2_CH4/EVENTOUT_70") (pintype "bidirectional+no_connect"))
    )
    (net (code "98") (name "unconnected-(U1A-PB12{slash}SPI2_NSS{slash}I2S2_WS{slash}I2C2_SMBA{slash}USART3_CK{slash}TIM1_BKIN{slash}CAN2_RX{slash}OTG_HS_ULPI_D5{slash}ETH_RMII_TXD0{slash}ETH_MII_TXD0{slash}OTG_HS_ID{slash}EVENTOUT-Pad73)") (class "Default")
      (node (ref "U1") (pin "73") (pinfunction "PB12/SPI2_NSS/I2S2_WS/I2C2_SMBA/USART3_CK/TIM1_BKIN/CAN2_RX/OTG_HS_ULPI_D5/ETH_RMII_TXD0/ETH_MII_TXD0/OTG_HS_ID/EVENTOUT_73") (pintype "bidirectional+no_connect"))
    )
    (net (code "99") (name "unconnected-(U1A-PB13{slash}SPI2_SCK{slash}I2S2_CK{slash}USART3_CTS{slash}TIM1_CH1N{slash}CAN2_TX{slash}OTG_HS_ULPI_D6{slash}ETH_RMII_TXD1{slash}ETH_MII_TXD1{slash}EVENTOUT{slash}OTG_HS_VBUS-Pad74)") (class "Default")
      (node (ref "U1") (pin "74") (pinfunction "PB13/SPI2_SCK/I2S2_CK/USART3_CTS/TIM1_CH1N/CAN2_TX/OTG_HS_ULPI_D6/ETH_RMII_TXD1/ETH_MII_TXD1/EVENTOUT/OTG_HS_VBUS_74") (pintype "bidirectional+no_connect"))
    )
    (net (code "100") (name "unconnected-(U1B-PC0{slash}OTG_HS_ULPI_STP{slash}EVENTOUT{slash}ADC123_IN10-Pad26)") (class "Default")
      (node (ref "U1") (pin "26") (pinfunction "PC0/OTG_HS_ULPI_STP/EVENTOUT/ADC123_IN10_26") (pintype "bidirectional+no_connect"))
    )
    (net (code "101") (name "unconnected-(U1B-PC1{slash}ETH_MDC{slash}EVENTOUT{slash}ADC123_IN11-Pad27)") (class "Default")
      (node (ref "U1") (pin "27") (pinfunction "PC1/ETH_MDC/EVENTOUT/ADC123_IN11_27") (pintype "bidirectional+no_connect"))
    )
    (net (code "102") (name "unconnected-(U1B-PC2{slash}SPI2_MISO{slash}OTG_HS_ULPI_DIR{slash}TH_MII_TXD2{slash}I2S2ext_SD{slash}EVENTOUT{slash}ADC123_IN12-Pad28)") (class "Default")
      (node (ref "U1") (pin "28") (pinfunction "PC2/SPI2_MISO/OTG_HS_ULPI_DIR/TH_MII_TXD2/I2S2ext_SD/EVENTOUT/ADC123_IN12_28") (pintype "bidirectional+no_connect"))
    )
    (net (code "103") (name "unconnected-(U1B-PC3{slash}SPI2_MOSI{slash}I2S2_SD{slash}OTG_HS_ULPI_NXT{slash}ETH_MII_TX_CLK{slash}EVENTOUT{slash}ADC123_IN13-Pad29)") (class "Default")
      (node (ref "U1") (pin "29") (pinfunction "PC3/SPI2_MOSI/I2S2_SD/OTG_HS_ULPI_NXT/ETH_MII_TX_CLK/EVENTOUT/ADC123_IN13_29") (pintype "bidirectional+no_connect"))
    )
    (net (code "104") (name "unconnected-(U1B-PC4{slash}ETH_RMII_RX_D0{slash}ETH_MII_RX_D0{slash}EVENTOUT{slash}ADC12_IN14-Pad44)") (class "Default")
      (node (ref "U1") (pin "44") (pinfunction "PC4/ETH_RMII_RX_D0/ETH_MII_RX_D0/EVENTOUT/ADC12_IN14_44") (pintype "bidirectional+no_connect"))
    )
    (net (code "105") (name "unconnected-(U1B-PC5{slash}ETH_RMII_RX_D1{slash}ETH_MII_RX_D1{slash}EVENTOUT{slash}ADC12_IN15-Pad45)") (class "Default")
      (node (ref "U1") (pin "45") (pinfunction "PC5/ETH_RMII_RX_D1/ETH_MII_RX_D1/EVENTOUT/ADC12_IN15_45") (pintype "bidirectional+no_connect"))
    )
    (net (code "106") (name "unconnected-(U1B-PC10{slash}SPI3_SCK{slash}I2S3_CK{slash}UART4_TX{slash}SDIO_D2{slash}DCMI_D8{slash}USART3_TX{slash}EVENTOUT-Pad111)") (class "Default")
      (node (ref "U1") (pin "111") (pinfunction "PC10/SPI3_SCK/I2S3_CK/UART4_TX/SDIO_D2/DCMI_D8/USART3_TX/EVENTOUT_111") (pintype "bidirectional+no_connect"))
    )
    (net (code "107") (name "unconnected-(U1B-PC12{slash}UART5_TX{slash}SDIO_CK{slash}DCMI_D9{slash}SPI3_MOSI{slash}I2S3_SD{slash}USART3_CK{slash}EVENTOUT-Pad113)") (class "Default")
      (node (ref "U1") (pin "113") (pinfunction "PC12/UART5_TX/SDIO_CK/DCMI_D9/SPI3_MOSI/I2S3_SD/USART3_CK/EVENTOUT_113") (pintype "bidirectional+no_connect"))
    )
    (net (code "108") (name "unconnected-(U1B-PC14-OSC32_IN(PC14){slash}EVENTOUT{slash}OSC32_IN-Pad8)") (class "Default")
      (node (ref "U1") (pin "8") (pinfunction "PC14-OSC32_IN(PC14)/EVENTOUT/OSC32_IN_8") (pintype "bidirectional+no_connect"))
    )
    (net (code "109") (name "unconnected-(U1B-PC15-OSC32_OUT(PC15){slash}EVENTOUT{slash}OSC32_OUT-Pad9)") (class "Default")
      (node (ref "U1") (pin "9") (pinfunction "PC15-OSC32_OUT(PC15)/EVENTOUT/OSC32_OUT_9") (pintype "bidirectional+no_connect"))
    )
    (net (code "110") (name "unconnected-(U1B-PD2{slash}TIM3_ETR{slash}UART5_RX{slash}SDIO_CMD{slash}DCMI_D11{slash}EVENTOUT-Pad116)") (class "Default")
      (node (ref "U1") (pin "116") (pinfunction "PD2/TIM3_ETR/UART5_RX/SDIO_CMD/DCMI_D11/EVENTOUT_116") (pintype "bidirectional+no_connect"))
    )
    (net (code "111") (name "unconnected-(U1B-PD3{slash}FSMC_CLK{slash}USART2_CTS{slash}EVENTOUT-Pad117)") (class "Default")
      (node (ref "U1") (pin "117") (pinfunction "PD3/FSMC_CLK/USART2_CTS/EVENTOUT_117") (pintype "bidirectional+no_connect"))
    )
    (net (code "112") (name "unconnected-(U1C-PF6{slash}TIM10_CH1{slash}FSMC_NIORD{slash}EVENTOUT{slash}ADC3_IN4-Pad18)") (class "Default")
      (node (ref "U1") (pin "18") (pinfunction "PF6/TIM10_CH1/FSMC_NIORD/EVENTOUT/ADC3_IN4_18") (pintype "bidirectional+no_connect"))
    )
    (net (code "113") (name "unconnected-(U1C-PF7{slash}TIM11_CH1{slash}FSMC_NREG{slash}EVENTOUT{slash}ADC3_IN5-Pad19)") (class "Default")
      (node (ref "U1") (pin "19") (pinfunction "PF7/TIM11_CH1/FSMC_NREG/EVENTOUT/ADC3_IN5_19") (pintype "bidirectional+no_connect"))
    )
    (net (code "114") (name "unconnected-(U1C-PF8{slash}TIM13_CH1{slash}FSMC_NIOWR{slash}EVENTOUT{slash}ADC3_IN6-Pad20)") (class "Default")
      (node (ref "U1") (pin "20") (pinfunction "PF8/TIM13_CH1/FSMC_NIOWR/EVENTOUT/ADC3_IN6_20") (pintype "bidirectional+no_connect"))
    )
    (net (code "115") (name "unconnected-(U1C-PF9{slash}TIM14_CH1{slash}FSMC_CD{slash}EVENTOUT{slash}ADC3_IN7-Pad21)") (class "Default")
      (node (ref "U1") (pin "21") (pinfunction "PF9/TIM14_CH1/FSMC_CD/EVENTOUT/ADC3_IN7_21") (pintype "bidirectional+no_connect"))
    )
    (net (code "116") (name "unconnected-(U1C-PF10{slash}FSMC_INTR{slash}EVENTOUT{slash}ADC3_IN8-Pad22)") (class "Default")
      (node (ref "U1") (pin "22") (pinfunction "PF10/FSMC_INTR/EVENTOUT/ADC3_IN8_22") (pintype "bidirectional+no_connect"))
    )
    (net (code "117") (name "unconnected-(U1D-PG6{slash}FSMC_INT2{slash}EVENTOUT-Pad91)") (class "Default")
      (node (ref "U1") (pin "91") (pinfunction "PG6/FSMC_INT2/EVENTOUT_91") (pintype "bidirectional+no_connect"))
    )
    (net (code "118") (name "unconnected-(U1D-PG7{slash}FSMC_INT3{slash}USART6_CK{slash}EVENTOUT-Pad92)") (class "Default")
      (node (ref "U1") (pin "92") (pinfunction "PG7/FSMC_INT3/USART6_CK/EVENTOUT_92") (pintype "bidirectional+no_connect"))
    )
    (net (code "119") (name "unconnected-(U1D-PG8{slash}USART6_RTS{slash}ETH_PPS_OUT{slash}EVENTOUT-Pad93)") (class "Default")
      (node (ref "U1") (pin "93") (pinfunction "PG8/USART6_RTS/ETH_PPS_OUT/EVENTOUT_93") (pintype "bidirectional+no_connect"))
    )
    (net (code "120") (name "unconnected-(U1D-PG11{slash}FSMC_NCE4_2{slash}ETH_MII_TX_EN{slash}ETH_RMII_TX_EN{slash}EVENTOUT-Pad126)") (class "Default")
      (node (ref "U1") (pin "126") (pinfunction "PG11/FSMC_NCE4_2/ETH_MII_TX_EN/ETH_RMII_TX_EN/EVENTOUT_126") (pintype "bidirectional+no_connect"))
    )
    (net (code "121") (name "unconnected-(U1D-PG13{slash}FSMC_A24{slash}USART6_CTS{slash}ETH_MII_TXD0{slash}ETH_RMII_TXD0{slash}EVENTOUT-Pad128)") (class "Default")
      (node (ref "U1") (pin "128") (pinfunction "PG13/FSMC_A24/USART6_CTS/ETH_MII_TXD0/ETH_RMII_TXD0/EVENTOUT_128") (pintype "bidirectional+no_connect"))
    )
    (net (code "122") (name "unconnected-(U1D-PG14{slash}FSMC_A25{slash}USART6_TX{slash}ETH_MII_TXD1{slash}ETH_RMII_TXD1{slash}EVENTOUT-Pad129)") (class "Default")
      (node (ref "U1") (pin "129") (pinfunction "PG14/FSMC_A25/USART6_TX/ETH_MII_TXD1/ETH_RMII_TXD1/EVENTOUT_129") (pintype "bidirectional+no_connect"))
    )
  )
)
